# main.net
KiCad netlist of a schematic drawn in Altium Designer
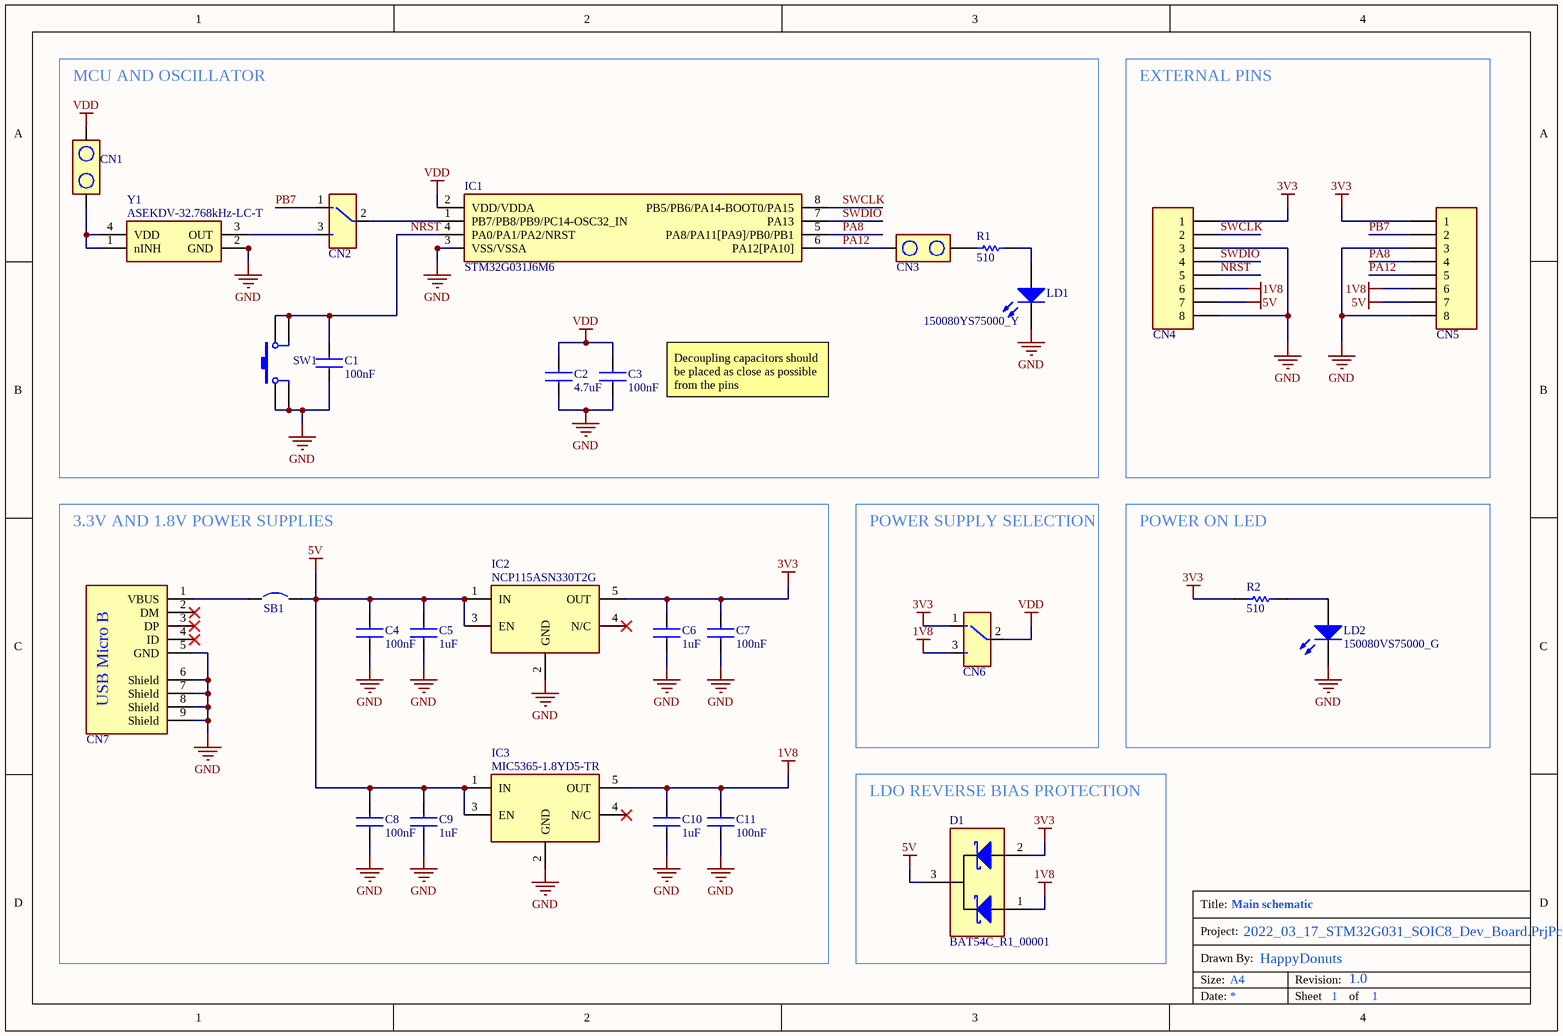
[diagram p0: main.SchDoc]

(export (version "E")
  (design (tool "Eeschema 10.0.6"))
  (components
    (comp (ref "C1")
      (value "100nF")
      (footprint "STM32G031_SOIC8_Dev_Board:CAPC2012X94N")
      (description "Capacitor")
      (fields
        (field (name "MANUFACTURER_PART_NUMBER") "C0805C104K5RAC7411")
        (field (name "MOUSER PART NUMBER") "80-C0805C104K5RACLR")
      )
      (libsource (lib "STM32G031_SOIC8_Dev_Board") (part "C0805C104K5RAC7411"))
    )
    (comp (ref "C2")
      (value "4.7uF")
      (footprint "STM32G031_SOIC8_Dev_Board:CAPC2012X135N")
      (description "Capacitor")
      (fields
        (field (name "MANUFACTURER_PART_NUMBER") "CL21A475KPFNNNE")
        (field (name "MOUSER PART NUMBER") "187-CL21A475KPFNNNE")
      )
      (libsource (lib "STM32G031_SOIC8_Dev_Board") (part "CL21A475KPFNNNE"))
    )
    (comp (ref "C3")
      (value "100nF")
      (footprint "STM32G031_SOIC8_Dev_Board:CAPC2012X94N")
      (description "Capacitor")
      (fields
        (field (name "MANUFACTURER_PART_NUMBER") "C0805C104K5RAC7411")
        (field (name "MOUSER PART NUMBER") "80-C0805C104K5RACLR")
      )
      (libsource (lib "STM32G031_SOIC8_Dev_Board") (part "C0805C104K5RAC7411"))
    )
    (comp (ref "C4")
      (value "100nF")
      (footprint "STM32G031_SOIC8_Dev_Board:CAPC2012X94N")
      (description "Capacitor")
      (fields
        (field (name "MANUFACTURER_PART_NUMBER") "C0805C104K5RAC7411")
        (field (name "MOUSER PART NUMBER") "80-C0805C104K5RACLR")
      )
      (libsource (lib "STM32G031_SOIC8_Dev_Board") (part "C0805C104K5RAC7411"))
    )
    (comp (ref "C5")
      (value "1uF")
      (footprint "STM32G031_SOIC8_Dev_Board:CAPC2012X135N")
      (description "Capacitor")
      (fields
        (field (name "MANUFACTURER_PART_NUMBER") "885012107015")
        (field (name "MOUSER PART NUMBER") "710-885012107015")
      )
      (libsource (lib "STM32G031_SOIC8_Dev_Board") (part "885012107015"))
    )
    (comp (ref "C6")
      (value "1uF")
      (footprint "STM32G031_SOIC8_Dev_Board:CAPC2012X135N")
      (description "Capacitor")
      (fields
        (field (name "MANUFACTURER_PART_NUMBER") "885012107015")
        (field (name "MOUSER PART NUMBER") "710-885012107015")
      )
      (libsource (lib "STM32G031_SOIC8_Dev_Board") (part "885012107015"))
    )
    (comp (ref "C7")
      (value "100nF")
      (footprint "STM32G031_SOIC8_Dev_Board:CAPC2012X94N")
      (description "Capacitor")
      (fields
        (field (name "MANUFACTURER_PART_NUMBER") "C0805C104K5RAC7411")
        (field (name "MOUSER PART NUMBER") "80-C0805C104K5RACLR")
      )
      (libsource (lib "STM32G031_SOIC8_Dev_Board") (part "C0805C104K5RAC7411"))
    )
    (comp (ref "C8")
      (value "100nF")
      (footprint "STM32G031_SOIC8_Dev_Board:CAPC2012X94N")
      (description "Capacitor")
      (fields
        (field (name "MANUFACTURER_PART_NUMBER") "C0805C104K5RAC7411")
        (field (name "MOUSER PART NUMBER") "80-C0805C104K5RACLR")
      )
      (libsource (lib "STM32G031_SOIC8_Dev_Board") (part "C0805C104K5RAC7411"))
    )
    (comp (ref "C9")
      (value "1uF")
      (footprint "STM32G031_SOIC8_Dev_Board:CAPC2012X135N")
      (description "Capacitor")
      (fields
        (field (name "MANUFACTURER_PART_NUMBER") "885012107015")
        (field (name "MOUSER PART NUMBER") "710-885012107015")
      )
      (libsource (lib "STM32G031_SOIC8_Dev_Board") (part "885012107015"))
    )
    (comp (ref "C10")
      (value "1uF")
      (footprint "STM32G031_SOIC8_Dev_Board:CAPC2012X135N")
      (description "Capacitor")
      (fields
        (field (name "MANUFACTURER_PART_NUMBER") "885012107015")
        (field (name "MOUSER PART NUMBER") "710-885012107015")
      )
      (libsource (lib "STM32G031_SOIC8_Dev_Board") (part "885012107015"))
    )
    (comp (ref "C11")
      (value "100nF")
      (footprint "STM32G031_SOIC8_Dev_Board:CAPC2012X94N")
      (description "Capacitor")
      (fields
        (field (name "MANUFACTURER_PART_NUMBER") "C0805C104K5RAC7411")
        (field (name "MOUSER PART NUMBER") "80-C0805C104K5RACLR")
      )
      (libsource (lib "STM32G031_SOIC8_Dev_Board") (part "C0805C104K5RAC7411"))
    )
    (comp (ref "CN1")
      (value "CN_2PIN")
      (footprint "STM32G031_SOIC8_Dev_Board:CN_2PIN")
      (description "Connector")
      (libsource (lib "STM32G031_SOIC8_Dev_Board") (part "CN_2PIN"))
    )
    (comp (ref "CN2")
      (value "CN_3PIN")
      (footprint "STM32G031_SOIC8_Dev_Board:CN_3PIN")
      (description "Connector")
      (libsource (lib "STM32G031_SOIC8_Dev_Board") (part "CN_3PIN"))
    )
    (comp (ref "CN3")
      (value "CN_2PIN")
      (footprint "STM32G031_SOIC8_Dev_Board:CN_2PIN")
      (description "Connector")
      (libsource (lib "") (part "CN_2PIN_1"))
    )
    (comp (ref "CN4")
      (value "CN_8PIN")
      (footprint "STM32G031_SOIC8_Dev_Board:CN_8PIN")
      (description "Connector")
      (libsource (lib "") (part "CN_8PIN_1"))
    )
    (comp (ref "CN5")
      (value "CN_8PIN")
      (footprint "STM32G031_SOIC8_Dev_Board:CN_8PIN")
      (description "Connector")
      (libsource (lib "STM32G031_SOIC8_Dev_Board") (part "CN_8PIN"))
    )
    (comp (ref "CN6")
      (value "CN_3PIN")
      (footprint "STM32G031_SOIC8_Dev_Board:CN_3PIN")
      (description "Connector")
      (libsource (lib "STM32G031_SOIC8_Dev_Board") (part "CN_3PIN"))
    )
    (comp (ref "CN7")
      (value "920-E52A2021S10100")
      (footprint "STM32G031_SOIC8_Dev_Board:USB307530A")
      (description "USB connector")
      (fields (field (name "ARROW PART NUMBER") "TB67H450FNG,EL"))
      (libsource (lib "STM32G031_SOIC8_Dev_Board") (part "920-E52A2021S10100"))
    )
    (comp (ref "D1")
      (value "BAT54C_R1_00001")
      (footprint "STM32G031_SOIC8_Dev_Board:SOT95P240X110-3N")
      (description "Schottky Diode")
      (fields (field (name "MOUSER PART NUMBER") "241-BAT54C_R1_00001"))
      (libsource (lib "STM32G031_SOIC8_Dev_Board") (part "BAT54C_R1_00001"))
    )
    (comp (ref "IC1")
      (value "STM32G031J6M6")
      (footprint "STM32G031_SOIC8_Dev_Board:SOIC127P600X175-8N")
      (description "Integrated Circuit")
      (fields (field (name "MOUSER PART NUMBER") "511-STM32G031J6M6"))
      (libsource (lib "STM32G031_SOIC8_Dev_Board") (part "STM32G031J6M6"))
    )
    (comp (ref "IC2")
      (value "NCP115ASN330T2G")
      (footprint "STM32G031_SOIC8_Dev_Board:SOT95P275X110-5N")
      (description "Integrated Circuit")
      (fields (field (name "MOUSER PART NUMBER") "863-NCP115ASN330T2G"))
      (libsource (lib "STM32G031_SOIC8_Dev_Board") (part "NCP115ASN330T2G"))
    )
    (comp (ref "IC3")
      (value "MIC5365-1.8YD5-TR")
      (footprint "STM32G031_SOIC8_Dev_Board:SOT95P275X110-5N")
      (description "Integrated Circuit")
      (fields (field (name "MOUSER PART NUMBER") "998-MIC5365-1.8YD5TR"))
      (libsource (lib "STM32G031_SOIC8_Dev_Board") (part "MIC5365-1.8YD5-TR"))
    )
    (comp (ref "LD1")
      (value "150080YS75000_Y")
      (footprint "STM32G031_SOIC8_Dev_Board:LEDC2012X85N_Y")
      (description "LED")
      (fields
        (field (name "MANUFACTURER_PART_NUMBER") "150080YS75000")
        (field (name "MOUSER PART NUMBER") "710-150080YS75000")
      )
      (libsource (lib "STM32G031_SOIC8_Dev_Board") (part "150080YS75000_Y"))
    )
    (comp (ref "LD2")
      (value "150080VS75000_G")
      (footprint "STM32G031_SOIC8_Dev_Board:LEDC2012X85N_G")
      (description "LED")
      (fields
        (field (name "MANUFACTURER_PART_NUMBER") "150080VS75000")
        (field (name "MOUSER PART NUMBER") "710-150080VS75000")
      )
      (libsource (lib "STM32G031_SOIC8_Dev_Board") (part "150080VS75000_G"))
    )
    (comp (ref "R1")
      (value "510")
      (footprint "STM32G031_SOIC8_Dev_Board:RESC2012X60N")
      (description "Resistor")
      (fields
        (field (name "MANUFACTURER_PART_NUMBER") "RC0805FR-07510RL")
        (field (name "MOUSER PART NUMBER") "603-RC0805FR-07510RL")
      )
      (libsource (lib "STM32G031_SOIC8_Dev_Board") (part "RC0805FR-07510RL"))
    )
    (comp (ref "R2")
      (value "510")
      (footprint "STM32G031_SOIC8_Dev_Board:RESC2012X60N")
      (description "Resistor")
      (fields
        (field (name "MANUFACTURER_PART_NUMBER") "RC0805FR-07510RL")
        (field (name "MOUSER PART NUMBER") "603-RC0805FR-07510RL")
      )
      (libsource (lib "STM32G031_SOIC8_Dev_Board") (part "RC0805FR-07510RL"))
    )
    (comp (ref "SB1")
      (value "RC0805FR-070RL")
      (footprint "STM32G031_SOIC8_Dev_Board:RESC2012X60N")
      (description "Jumper (0 ohm)")
      (fields (field (name "MOUSER PART NUMBER") "603-RC0805FR-070RL"))
      (libsource (lib "STM32G031_SOIC8_Dev_Board") (part "RC0805FR-070RL"))
    )
    (comp (ref "SW1")
      (value "EVP-BT3G4A000")
      (footprint "STM32G031_SOIC8_Dev_Board:EVP-BT3G4A000")
      (description "Tactile switch")
      (libsource (lib "STM32G031_SOIC8_Dev_Board") (part "EVP-BT3G4A000"))
    )
    (comp (ref "Y1")
      (value "ASEKDV-32.768kHz-LC-T")
      (footprint "STM32G031_SOIC8_Dev_Board:ASEKDV-32.768kHz-LC-T")
      (description "Crystal or Oscillator")
      (fields (field (name "MOUSER PART NUMBER") "815-ASEKDV32768KHLCT"))
      (libsource (lib "STM32G031_SOIC8_Dev_Board") (part "ASEKDV-32.768kHz-LC-T"))
    )
  )
  (nets
    (net (code "1") (name "/NRST") (class "Default")
      (node (ref "C1") (pin "2") (pinfunction "2_2") (pintype "passive"))
      (node (ref "CN4") (pin "5") (pinfunction "5_5") (pintype "passive"))
      (node (ref "IC1") (pin "4") (pinfunction "PA0/PA1/PA2/NRST_4") (pintype "passive"))
      (node (ref "SW1") (pin "3") (pinfunction "3_3") (pintype "passive"))
      (node (ref "SW1") (pin "4") (pinfunction "4_4") (pintype "passive"))
    )
    (net (code "2") (name "/PA8") (class "Default")
      (node (ref "CN5") (pin "4") (pinfunction "4_4") (pintype "passive"))
      (node (ref "IC1") (pin "5") (pinfunction "PA8/PA11[PA9]/PB0/PB1_5") (pintype "passive"))
    )
    (net (code "3") (name "/PA12") (class "Default")
      (node (ref "CN3") (pin "1") (pinfunction "1_1") (pintype "passive"))
      (node (ref "CN5") (pin "5") (pinfunction "5_5") (pintype "passive"))
      (node (ref "IC1") (pin "6") (pinfunction "PA12[PA10]_6") (pintype "passive"))
    )
    (net (code "4") (name "/PB7") (class "Default")
      (node (ref "CN2") (pin "1") (pinfunction "1_1") (pintype "passive"))
      (node (ref "CN5") (pin "2") (pinfunction "2_2") (pintype "passive"))
    )
    (net (code "5") (name "/SWCLK") (class "Default")
      (node (ref "CN4") (pin "2") (pinfunction "2_2") (pintype "passive"))
      (node (ref "IC1") (pin "8") (pinfunction "PB5/PB6/PA14-BOOT0/PA15_8") (pintype "passive"))
    )
    (net (code "6") (name "/SWDIO") (class "Default")
      (node (ref "CN4") (pin "4") (pinfunction "4_4") (pintype "passive"))
      (node (ref "IC1") (pin "7") (pinfunction "PA13_7") (pintype "passive"))
    )
    (net (code "7") (name "1V8") (class "Default")
      (node (ref "C10") (pin "2") (pinfunction "2_2") (pintype "passive"))
      (node (ref "C11") (pin "2") (pinfunction "2_2") (pintype "passive"))
      (node (ref "CN4") (pin "6") (pinfunction "6_6") (pintype "passive"))
      (node (ref "CN5") (pin "6") (pinfunction "6_6") (pintype "passive"))
      (node (ref "CN6") (pin "3") (pinfunction "3_3") (pintype "passive"))
      (node (ref "D1") (pin "1") (pinfunction "K_1_1") (pintype "passive"))
      (node (ref "IC3") (pin "5") (pinfunction "OUT_5") (pintype "passive"))
    )
    (net (code "8") (name "3V3") (class "Default")
      (node (ref "C6") (pin "2") (pinfunction "2_2") (pintype "passive"))
      (node (ref "C7") (pin "2") (pinfunction "2_2") (pintype "passive"))
      (node (ref "CN4") (pin "1") (pinfunction "1_1") (pintype "passive"))
      (node (ref "CN5") (pin "1") (pinfunction "1_1") (pintype "passive"))
      (node (ref "CN6") (pin "1") (pinfunction "1_1") (pintype "passive"))
      (node (ref "D1") (pin "2") (pinfunction "K_2_2") (pintype "passive"))
      (node (ref "IC2") (pin "5") (pinfunction "OUT_5") (pintype "passive"))
      (node (ref "R2") (pin "1") (pinfunction "1_1") (pintype "passive"))
    )
    (net (code "9") (name "5V") (class "Default")
      (node (ref "C4") (pin "2") (pinfunction "2_2") (pintype "passive"))
      (node (ref "C5") (pin "2") (pinfunction "2_2") (pintype "passive"))
      (node (ref "C8") (pin "2") (pinfunction "2_2") (pintype "passive"))
      (node (ref "C9") (pin "2") (pinfunction "2_2") (pintype "passive"))
      (node (ref "CN4") (pin "7") (pinfunction "7_7") (pintype "passive"))
      (node (ref "CN5") (pin "7") (pinfunction "7_7") (pintype "passive"))
      (node (ref "D1") (pin "3") (pinfunction "COM_A_3") (pintype "passive"))
      (node (ref "IC2") (pin "1") (pinfunction "IN_1") (pintype "passive"))
      (node (ref "IC2") (pin "3") (pinfunction "EN_3") (pintype "passive"))
      (node (ref "IC3") (pin "1") (pinfunction "IN_1") (pintype "passive"))
      (node (ref "IC3") (pin "3") (pinfunction "EN_3") (pintype "passive"))
      (node (ref "SB1") (pin "2") (pinfunction "2_2") (pintype "passive"))
    )
    (net (code "10") (name "GND") (class "Default")
      (node (ref "C1") (pin "1") (pinfunction "1_1") (pintype "passive"))
      (node (ref "C10") (pin "1") (pinfunction "1_1") (pintype "passive"))
      (node (ref "C11") (pin "1") (pinfunction "1_1") (pintype "passive"))
      (node (ref "C2") (pin "1") (pinfunction "1_1") (pintype "passive"))
      (node (ref "C3") (pin "1") (pinfunction "1_1") (pintype "passive"))
      (node (ref "C4") (pin "1") (pinfunction "1_1") (pintype "passive"))
      (node (ref "C5") (pin "1") (pinfunction "1_1") (pintype "passive"))
      (node (ref "C6") (pin "1") (pinfunction "1_1") (pintype "passive"))
      (node (ref "C7") (pin "1") (pinfunction "1_1") (pintype "passive"))
      (node (ref "C8") (pin "1") (pinfunction "1_1") (pintype "passive"))
      (node (ref "C9") (pin "1") (pinfunction "1_1") (pintype "passive"))
      (node (ref "CN4") (pin "3") (pinfunction "3_3") (pintype "passive"))
      (node (ref "CN4") (pin "8") (pinfunction "8_8") (pintype "passive"))
      (node (ref "CN5") (pin "3") (pinfunction "3_3") (pintype "passive"))
      (node (ref "CN5") (pin "8") (pinfunction "8_8") (pintype "passive"))
      (node (ref "CN7") (pin "5") (pinfunction "GND_5") (pintype "passive"))
      (node (ref "CN7") (pin "6") (pinfunction "Shield_6") (pintype "passive"))
      (node (ref "CN7") (pin "7") (pinfunction "Shield_7") (pintype "passive"))
      (node (ref "CN7") (pin "8") (pinfunction "Shield_8") (pintype "passive"))
      (node (ref "CN7") (pin "9") (pinfunction "Shield_9") (pintype "passive"))
      (node (ref "IC1") (pin "3") (pinfunction "VSS/VSSA_3") (pintype "passive"))
      (node (ref "IC2") (pin "2") (pinfunction "GND_2") (pintype "passive"))
      (node (ref "IC3") (pin "2") (pinfunction "GND_2") (pintype "passive"))
      (node (ref "LD1") (pin "1") (pinfunction "K_1") (pintype "passive"))
      (node (ref "LD2") (pin "1") (pinfunction "K_1") (pintype "passive"))
      (node (ref "SW1") (pin "1") (pinfunction "1_1") (pintype "passive"))
      (node (ref "SW1") (pin "2") (pinfunction "2_2") (pintype "passive"))
      (node (ref "Y1") (pin "2") (pinfunction "GND_2") (pintype "passive"))
    )
    (net (code "11") (name "Net-(CN3-Pad2)") (class "Default")
      (node (ref "CN3") (pin "2") (pinfunction "2_2") (pintype "passive"))
      (node (ref "R1") (pin "1") (pinfunction "1_1") (pintype "passive"))
    )
    (net (code "12") (name "Net-(CN7-VBUS)") (class "Default")
      (node (ref "CN7") (pin "1") (pinfunction "VBUS_1") (pintype "passive"))
      (node (ref "SB1") (pin "1") (pinfunction "1_1") (pintype "passive"))
    )
    (net (code "13") (name "Net-(IC1-PB7{slash}PB8{slash}PB9{slash}PC14-OSC32_IN)") (class "Default")
      (node (ref "CN2") (pin "2") (pinfunction "2_2") (pintype "passive"))
      (node (ref "IC1") (pin "1") (pinfunction "PB7/PB8/PB9/PC14-OSC32_IN_1") (pintype "passive"))
    )
    (net (code "14") (name "Net-(LD1-A)") (class "Default")
      (node (ref "LD1") (pin "2") (pinfunction "A_2") (pintype "passive"))
      (node (ref "R1") (pin "2") (pinfunction "2_2") (pintype "passive"))
    )
    (net (code "15") (name "Net-(LD2-A)") (class "Default")
      (node (ref "LD2") (pin "2") (pinfunction "A_2") (pintype "passive"))
      (node (ref "R2") (pin "2") (pinfunction "2_2") (pintype "passive"))
    )
    (net (code "16") (name "Net-(Y1-OUT)") (class "Default")
      (node (ref "CN2") (pin "3") (pinfunction "3_3") (pintype "passive"))
      (node (ref "Y1") (pin "3") (pinfunction "OUT_3") (pintype "passive"))
    )
    (net (code "17") (name "Net-(Y1-VDD)") (class "Default")
      (node (ref "CN1") (pin "1") (pinfunction "1_1") (pintype "passive"))
      (node (ref "Y1") (pin "1") (pinfunction "nINH_1") (pintype "passive"))
      (node (ref "Y1") (pin "4") (pinfunction "VDD_4") (pintype "passive"))
    )
    (net (code "18") (name "VDD") (class "Default")
      (node (ref "C2") (pin "2") (pinfunction "2_2") (pintype "passive"))
      (node (ref "C3") (pin "2") (pinfunction "2_2") (pintype "passive"))
      (node (ref "CN1") (pin "2") (pinfunction "2_2") (pintype "passive"))
      (node (ref "CN6") (pin "2") (pinfunction "2_2") (pintype "passive"))
      (node (ref "IC1") (pin "2") (pinfunction "VDD/VDDA_2") (pintype "passive"))
    )
    (net (code "19") (name "unconnected-(CN7-DM-Pad2)") (class "Default")
      (node (ref "CN7") (pin "2") (pinfunction "DM_2") (pintype "passive+no_connect"))
    )
    (net (code "20") (name "unconnected-(CN7-DP-Pad3)") (class "Default")
      (node (ref "CN7") (pin "3") (pinfunction "DP_3") (pintype "passive+no_connect"))
    )
    (net (code "21") (name "unconnected-(CN7-ID-Pad4)") (class "Default")
      (node (ref "CN7") (pin "4") (pinfunction "ID_4") (pintype "passive+no_connect"))
    )
    (net (code "22") (name "unconnected-(IC2-N{slash}C-Pad4)") (class "Default")
      (node (ref "IC2") (pin "4") (pinfunction "N/C_4") (pintype "passive+no_connect"))
    )
    (net (code "23") (name "unconnected-(IC3-N{slash}C-Pad4)") (class "Default")
      (node (ref "IC3") (pin "4") (pinfunction "N/C_4") (pintype "passive+no_connect"))
    )
  )
)
